# NIXIE_3.net
KiCad netlist of a schematic drawn in Altium Designer
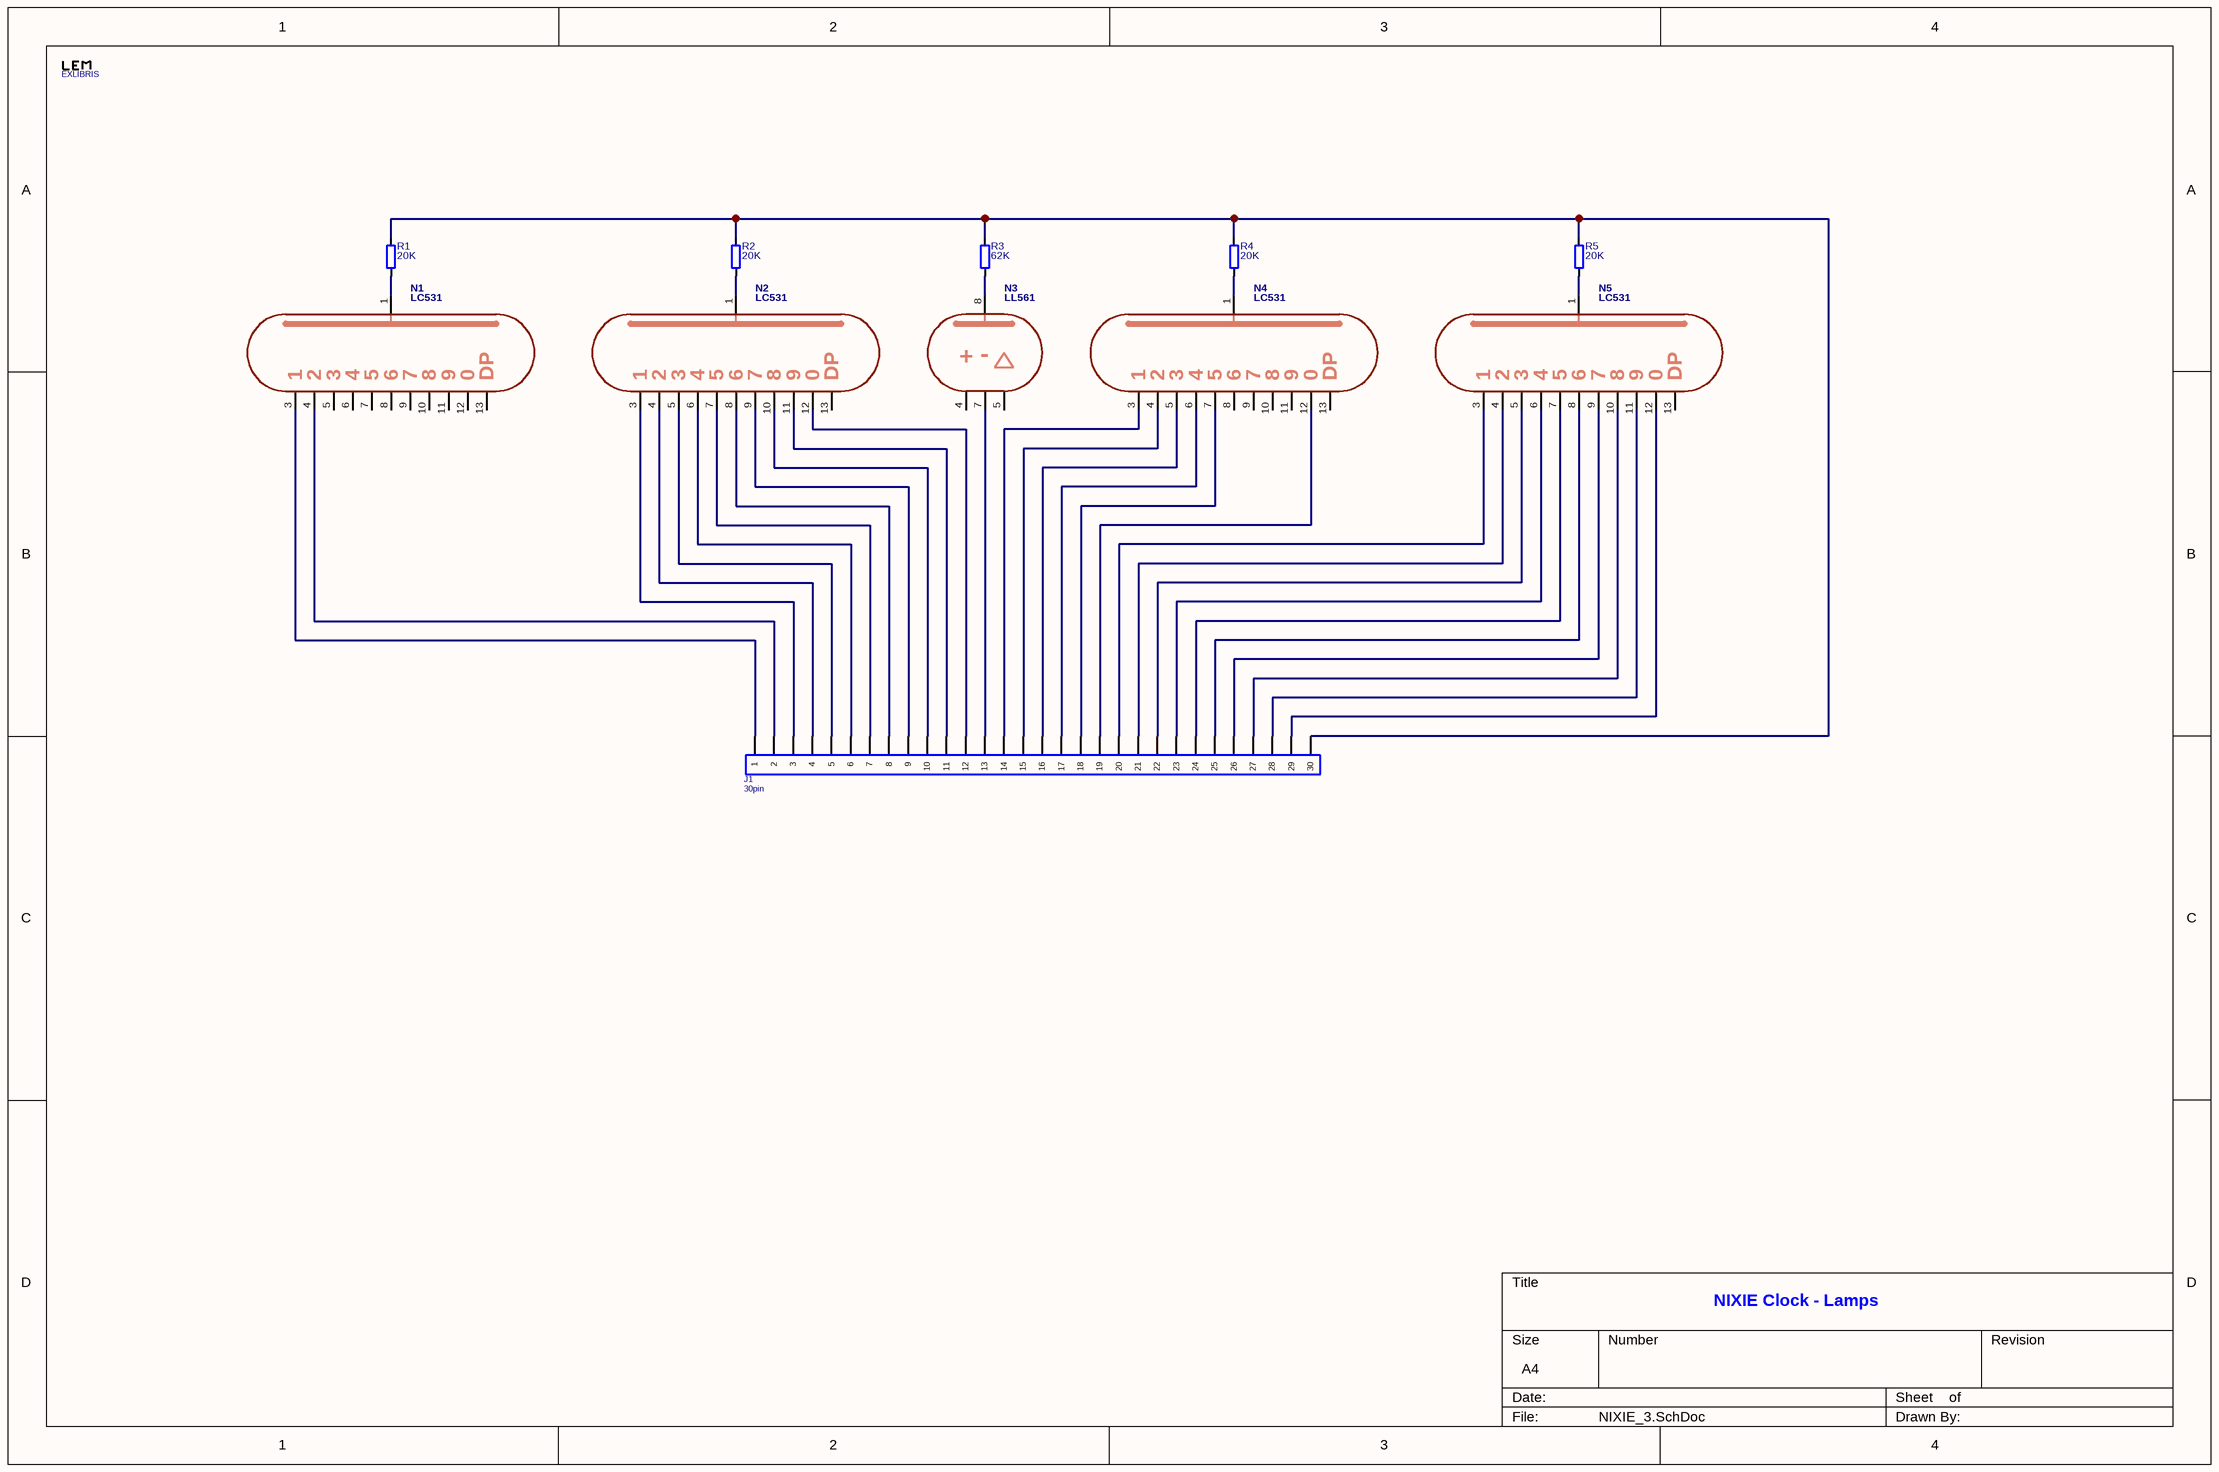
[diagram p0: NIXIE_3.SchDoc]

(export (version "E")
  (design (tool "Eeschema 10.0.6"))
  (components
    (comp (ref "EXLIBRIS") (value "EXLIBRIS") (footprint "EXLBS_2") (libsource (lib "Misc") (part "EXLBR")))
    (comp (ref "J1") (value "30pin") (footprint "SIL30") (libsource (lib "Connectors") (part "CON 30pin")))
    (comp (ref "N1")
      (value "LC531")
      (footprint "Nixie LC531")
      (description "Lampa Numeryczna Nixie")
      (libsource (lib "Wyswietlacze") (part "NIXIE LC531"))
    )
    (comp (ref "N2")
      (value "LC531")
      (footprint "Nixie LC531")
      (description "Lampa Numeryczna Nixie")
      (libsource (lib "Wyswietlacze") (part "NIXIE LC531"))
    )
    (comp (ref "N3")
      (value "LL561")
      (footprint "NIXIE LL561")
      (description "SIGN NEON LAMP")
      (libsource (lib "Wyswietlacze") (part "NIXIE LL561"))
    )
    (comp (ref "N4")
      (value "LC531")
      (footprint "Nixie LC531")
      (description "Lampa Numeryczna Nixie")
      (libsource (lib "Wyswietlacze") (part "NIXIE LC531"))
    )
    (comp (ref "N5")
      (value "LC531")
      (footprint "Nixie LC531")
      (description "Lampa Numeryczna Nixie")
      (libsource (lib "Wyswietlacze") (part "NIXIE LC531"))
    )
    (comp (ref "R1")
      (value "20K")
      (footprint "SMD_R_0805")
      (description "Resistor")
      (libsource (lib "Res") (part "R"))
    )
    (comp (ref "R2")
      (value "20K")
      (footprint "SMD_R_0805")
      (description "Resistor")
      (libsource (lib "Res") (part "R"))
    )
    (comp (ref "R3")
      (value "62K")
      (footprint "SMD_R_0805")
      (description "Resistor")
      (libsource (lib "Res") (part "R"))
    )
    (comp (ref "R4")
      (value "20K")
      (footprint "SMD_R_0805")
      (description "Resistor")
      (libsource (lib "Res") (part "R"))
    )
    (comp (ref "R5")
      (value "20K")
      (footprint "SMD_R_0805")
      (description "Resistor")
      (libsource (lib "Res") (part "R"))
    )
  )
  (nets
    (net (code "1") (name "Net-(J1-Pad30)") (class "Default")
      (node (ref "J1") (pin "30") (pinfunction "30_30") (pintype "passive"))
      (node (ref "R1") (pin "2") (pinfunction "2_2") (pintype "passive"))
      (node (ref "R2") (pin "2") (pinfunction "2_2") (pintype "passive"))
      (node (ref "R3") (pin "2") (pinfunction "2_2") (pintype "passive"))
      (node (ref "R4") (pin "2") (pinfunction "2_2") (pintype "passive"))
      (node (ref "R5") (pin "2") (pinfunction "2_2") (pintype "passive"))
    )
    (net (code "2") (name "Net-(N1-1)") (class "Default")
      (node (ref "J1") (pin "1") (pinfunction "1_1") (pintype "passive"))
      (node (ref "N1") (pin "3") (pinfunction "1_3") (pintype "passive"))
    )
    (net (code "3") (name "Net-(N1-2)") (class "Default")
      (node (ref "J1") (pin "2") (pinfunction "2_2") (pintype "passive"))
      (node (ref "N1") (pin "4") (pinfunction "2_4") (pintype "passive"))
    )
    (net (code "4") (name "Net-(N1-A)") (class "Default")
      (node (ref "N1") (pin "1") (pinfunction "A_1") (pintype "passive"))
      (node (ref "R1") (pin "1") (pinfunction "1_1") (pintype "passive"))
    )
    (net (code "5") (name "Net-(N2-0)") (class "Default")
      (node (ref "J1") (pin "12") (pinfunction "12_12") (pintype "passive"))
      (node (ref "N2") (pin "12") (pinfunction "0_12") (pintype "passive"))
    )
    (net (code "6") (name "Net-(N2-1)") (class "Default")
      (node (ref "J1") (pin "3") (pinfunction "3_3") (pintype "passive"))
      (node (ref "N2") (pin "3") (pinfunction "1_3") (pintype "passive"))
    )
    (net (code "7") (name "Net-(N2-2)") (class "Default")
      (node (ref "J1") (pin "4") (pinfunction "4_4") (pintype "passive"))
      (node (ref "N2") (pin "4") (pinfunction "2_4") (pintype "passive"))
    )
    (net (code "8") (name "Net-(N2-3)") (class "Default")
      (node (ref "J1") (pin "5") (pinfunction "5_5") (pintype "passive"))
      (node (ref "N2") (pin "5") (pinfunction "3_5") (pintype "passive"))
    )
    (net (code "9") (name "Net-(N2-4)") (class "Default")
      (node (ref "J1") (pin "6") (pinfunction "6_6") (pintype "passive"))
      (node (ref "N2") (pin "6") (pinfunction "4_6") (pintype "passive"))
    )
    (net (code "10") (name "Net-(N2-5)") (class "Default")
      (node (ref "J1") (pin "7") (pinfunction "7_7") (pintype "passive"))
      (node (ref "N2") (pin "7") (pinfunction "5_7") (pintype "passive"))
    )
    (net (code "11") (name "Net-(N2-6)") (class "Default")
      (node (ref "J1") (pin "8") (pinfunction "8_8") (pintype "passive"))
      (node (ref "N2") (pin "8") (pinfunction "6_8") (pintype "passive"))
    )
    (net (code "12") (name "Net-(N2-7)") (class "Default")
      (node (ref "J1") (pin "9") (pinfunction "9_9") (pintype "passive"))
      (node (ref "N2") (pin "9") (pinfunction "7_9") (pintype "passive"))
    )
    (net (code "13") (name "Net-(N2-8)") (class "Default")
      (node (ref "J1") (pin "10") (pinfunction "10_10") (pintype "passive"))
      (node (ref "N2") (pin "10") (pinfunction "8_10") (pintype "passive"))
    )
    (net (code "14") (name "Net-(N2-9)") (class "Default")
      (node (ref "J1") (pin "11") (pinfunction "11_11") (pintype "passive"))
      (node (ref "N2") (pin "11") (pinfunction "9_11") (pintype "passive"))
    )
    (net (code "15") (name "Net-(N2-A)") (class "Default")
      (node (ref "N2") (pin "1") (pinfunction "A_1") (pintype "passive"))
      (node (ref "R2") (pin "1") (pinfunction "1_1") (pintype "passive"))
    )
    (net (code "16") (name "Net-(N3--)") (class "Default")
      (node (ref "J1") (pin "13") (pinfunction "13_13") (pintype "passive"))
      (node (ref "N3") (pin "7") (pinfunction "-_7") (pintype "passive"))
    )
    (net (code "17") (name "Net-(N3-A)") (class "Default")
      (node (ref "N3") (pin "8") (pinfunction "A_8") (pintype "passive"))
      (node (ref "R3") (pin "1") (pinfunction "1_1") (pintype "passive"))
    )
    (net (code "18") (name "Net-(N4-0)") (class "Default")
      (node (ref "J1") (pin "19") (pinfunction "19_19") (pintype "passive"))
      (node (ref "N4") (pin "12") (pinfunction "0_12") (pintype "passive"))
    )
    (net (code "19") (name "Net-(N4-1)") (class "Default")
      (node (ref "J1") (pin "14") (pinfunction "14_14") (pintype "passive"))
      (node (ref "N4") (pin "3") (pinfunction "1_3") (pintype "passive"))
    )
    (net (code "20") (name "Net-(N4-2)") (class "Default")
      (node (ref "J1") (pin "15") (pinfunction "15_15") (pintype "passive"))
      (node (ref "N4") (pin "4") (pinfunction "2_4") (pintype "passive"))
    )
    (net (code "21") (name "Net-(N4-3)") (class "Default")
      (node (ref "J1") (pin "16") (pinfunction "16_16") (pintype "passive"))
      (node (ref "N4") (pin "5") (pinfunction "3_5") (pintype "passive"))
    )
    (net (code "22") (name "Net-(N4-4)") (class "Default")
      (node (ref "J1") (pin "17") (pinfunction "17_17") (pintype "passive"))
      (node (ref "N4") (pin "6") (pinfunction "4_6") (pintype "passive"))
    )
    (net (code "23") (name "Net-(N4-5)") (class "Default")
      (node (ref "J1") (pin "18") (pinfunction "18_18") (pintype "passive"))
      (node (ref "N4") (pin "7") (pinfunction "5_7") (pintype "passive"))
    )
    (net (code "24") (name "Net-(N4-A)") (class "Default")
      (node (ref "N4") (pin "1") (pinfunction "A_1") (pintype "passive"))
      (node (ref "R4") (pin "1") (pinfunction "1_1") (pintype "passive"))
    )
    (net (code "25") (name "Net-(N5-0)") (class "Default")
      (node (ref "J1") (pin "29") (pinfunction "29_29") (pintype "passive"))
      (node (ref "N5") (pin "12") (pinfunction "0_12") (pintype "passive"))
    )
    (net (code "26") (name "Net-(N5-1)") (class "Default")
      (node (ref "J1") (pin "20") (pinfunction "20_20") (pintype "passive"))
      (node (ref "N5") (pin "3") (pinfunction "1_3") (pintype "passive"))
    )
    (net (code "27") (name "Net-(N5-2)") (class "Default")
      (node (ref "J1") (pin "21") (pinfunction "21_21") (pintype "passive"))
      (node (ref "N5") (pin "4") (pinfunction "2_4") (pintype "passive"))
    )
    (net (code "28") (name "Net-(N5-3)") (class "Default")
      (node (ref "J1") (pin "22") (pinfunction "22_22") (pintype "passive"))
      (node (ref "N5") (pin "5") (pinfunction "3_5") (pintype "passive"))
    )
    (net (code "29") (name "Net-(N5-4)") (class "Default")
      (node (ref "J1") (pin "23") (pinfunction "23_23") (pintype "passive"))
      (node (ref "N5") (pin "6") (pinfunction "4_6") (pintype "passive"))
    )
    (net (code "30") (name "Net-(N5-5)") (class "Default")
      (node (ref "J1") (pin "24") (pinfunction "24_24") (pintype "passive"))
      (node (ref "N5") (pin "7") (pinfunction "5_7") (pintype "passive"))
    )
    (net (code "31") (name "Net-(N5-6)") (class "Default")
      (node (ref "J1") (pin "25") (pinfunction "25_25") (pintype "passive"))
      (node (ref "N5") (pin "8") (pinfunction "6_8") (pintype "passive"))
    )
    (net (code "32") (name "Net-(N5-7)") (class "Default")
      (node (ref "J1") (pin "26") (pinfunction "26_26") (pintype "passive"))
      (node (ref "N5") (pin "9") (pinfunction "7_9") (pintype "passive"))
    )
    (net (code "33") (name "Net-(N5-8)") (class "Default")
      (node (ref "J1") (pin "27") (pinfunction "27_27") (pintype "passive"))
      (node (ref "N5") (pin "10") (pinfunction "8_10") (pintype "passive"))
    )
    (net (code "34") (name "Net-(N5-9)") (class "Default")
      (node (ref "J1") (pin "28") (pinfunction "28_28") (pintype "passive"))
      (node (ref "N5") (pin "11") (pinfunction "9_11") (pintype "passive"))
    )
    (net (code "35") (name "Net-(N5-A)") (class "Default")
      (node (ref "N5") (pin "1") (pinfunction "A_1") (pintype "passive"))
      (node (ref "R5") (pin "1") (pinfunction "1_1") (pintype "passive"))
    )
    (net (code "36") (name "unconnected-(N1-0-Pad12)") (class "Default")
      (node (ref "N1") (pin "12") (pinfunction "0_12") (pintype "passive"))
    )
    (net (code "37") (name "unconnected-(N1-3-Pad5)") (class "Default")
      (node (ref "N1") (pin "5") (pinfunction "3_5") (pintype "passive"))
    )
    (net (code "38") (name "unconnected-(N1-4-Pad6)") (class "Default")
      (node (ref "N1") (pin "6") (pinfunction "4_6") (pintype "passive"))
    )
    (net (code "39") (name "unconnected-(N1-5-Pad7)") (class "Default")
      (node (ref "N1") (pin "7") (pinfunction "5_7") (pintype "passive"))
    )
    (net (code "40") (name "unconnected-(N1-6-Pad8)") (class "Default")
      (node (ref "N1") (pin "8") (pinfunction "6_8") (pintype "passive"))
    )
    (net (code "41") (name "unconnected-(N1-7-Pad9)") (class "Default")
      (node (ref "N1") (pin "9") (pinfunction "7_9") (pintype "passive"))
    )
    (net (code "42") (name "unconnected-(N1-8-Pad10)") (class "Default")
      (node (ref "N1") (pin "10") (pinfunction "8_10") (pintype "passive"))
    )
    (net (code "43") (name "unconnected-(N1-9-Pad11)") (class "Default")
      (node (ref "N1") (pin "11") (pinfunction "9_11") (pintype "passive"))
    )
    (net (code "44") (name "unconnected-(N1-DP-Pad13)") (class "Default")
      (node (ref "N1") (pin "13") (pinfunction "DP_13") (pintype "passive"))
    )
    (net (code "45") (name "unconnected-(N2-DP-Pad13)") (class "Default")
      (node (ref "N2") (pin "13") (pinfunction "DP_13") (pintype "passive"))
    )
    (net (code "46") (name "unconnected-(N3-+-Pad4)") (class "Default")
      (node (ref "N3") (pin "4") (pinfunction "+_4") (pintype "passive"))
    )
    (net (code "47") (name "unconnected-(N3-DELTA-Pad5)") (class "Default")
      (node (ref "N3") (pin "5") (pinfunction "DELTA_5") (pintype "passive"))
    )
    (net (code "48") (name "unconnected-(N4-6-Pad8)") (class "Default")
      (node (ref "N4") (pin "8") (pinfunction "6_8") (pintype "passive"))
    )
    (net (code "49") (name "unconnected-(N4-7-Pad9)") (class "Default")
      (node (ref "N4") (pin "9") (pinfunction "7_9") (pintype "passive"))
    )
    (net (code "50") (name "unconnected-(N4-8-Pad10)") (class "Default")
      (node (ref "N4") (pin "10") (pinfunction "8_10") (pintype "passive"))
    )
    (net (code "51") (name "unconnected-(N4-9-Pad11)") (class "Default")
      (node (ref "N4") (pin "11") (pinfunction "9_11") (pintype "passive"))
    )
    (net (code "52") (name "unconnected-(N4-DP-Pad13)") (class "Default")
      (node (ref "N4") (pin "13") (pinfunction "DP_13") (pintype "passive"))
    )
    (net (code "53") (name "unconnected-(N5-DP-Pad13)") (class "Default")
      (node (ref "N5") (pin "13") (pinfunction "DP_13") (pintype "passive"))
    )
  )
)
